# 01_Connector.net
KiCad netlist of a schematic drawn in Altium Designer
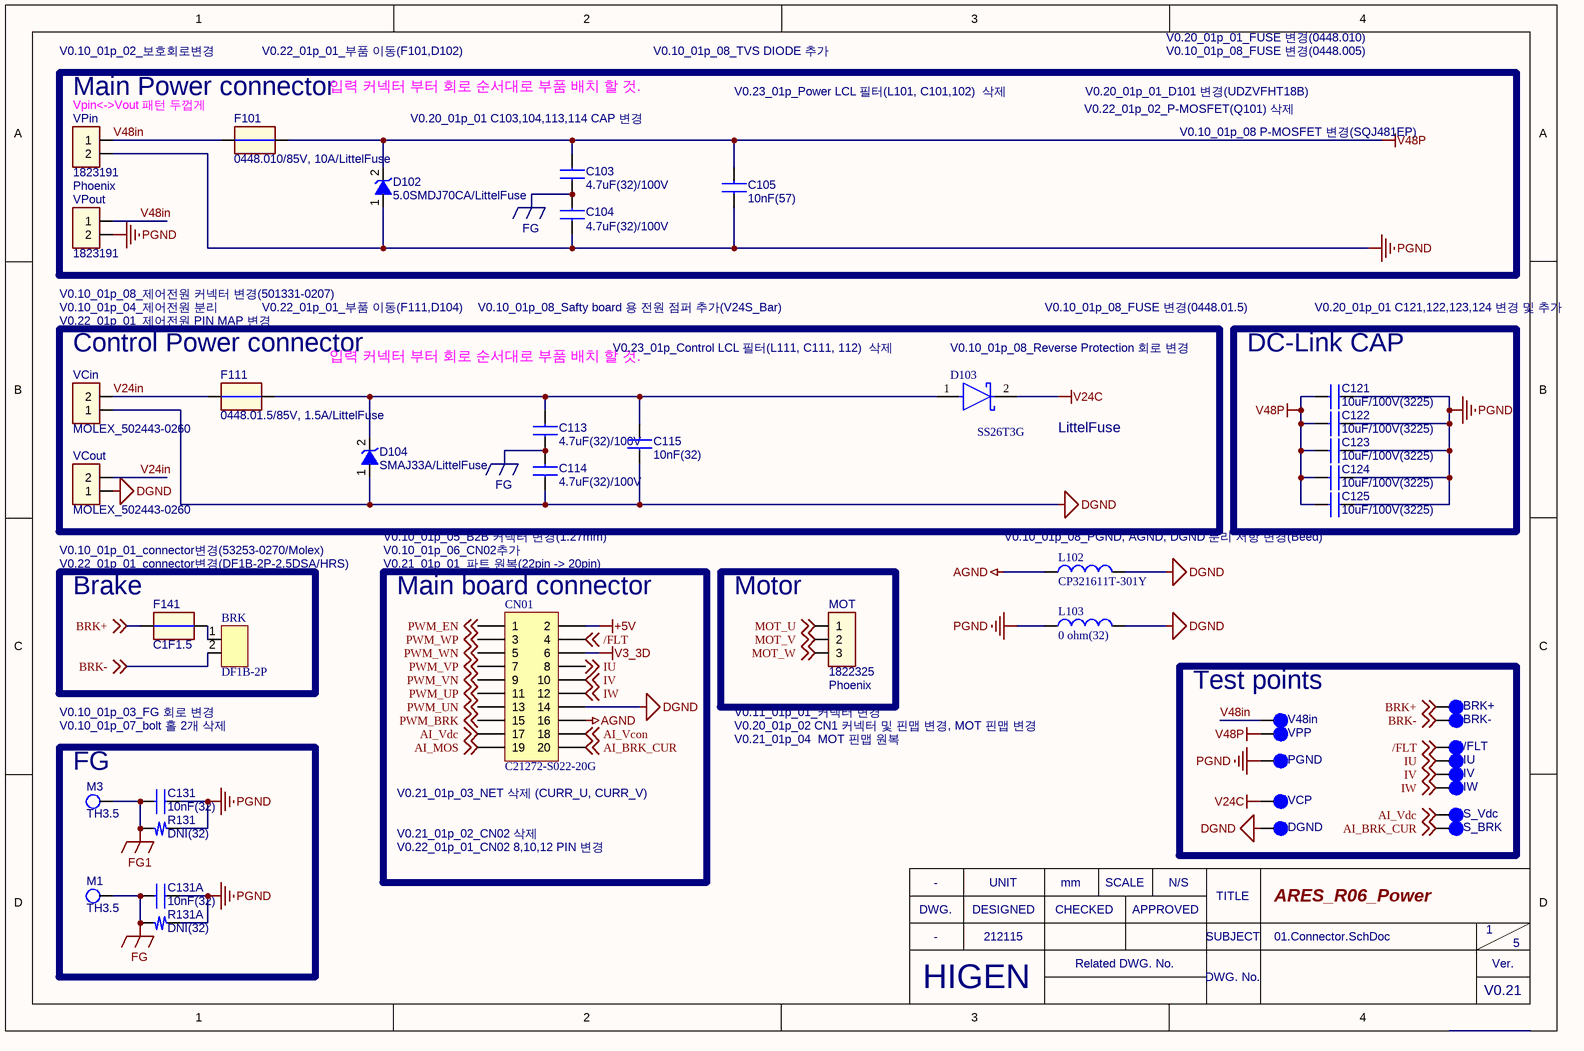
[diagram p0: 01.Connector.SchDoc]

(export (version "E")
  (design (tool "Eeschema 10.0.6"))
  (components
    (comp (ref "/FLT")
      (value "TP")
      (footprint "TP-SMD")
      (libsource (lib "*") (part "2H_TestPointThroughHole"))
    )
    (comp (ref "BRK")
      (value "DF1B-2P")
      (footprint "DF1B-2P-2.5DSA")
      (libsource (lib "DF1BB") (part "Component_1"))
    )
    (comp (ref "BRK+")
      (value "TP")
      (footprint "TP-SMD")
      (libsource (lib "*") (part "2H_TestPointThroughHole"))
    )
    (comp (ref "BRK-")
      (value "TP")
      (footprint "TP-SMD")
      (libsource (lib "*") (part "2H_TestPointThroughHole"))
    )
    (comp (ref "C103")
      (value "4.7uF(32)/100V")
      (footprint "C-3216S")
      (libsource (lib "HIGEN") (part "Cap_NP"))
    )
    (comp (ref "C104")
      (value "4.7uF(32)/100V")
      (footprint "C-3216S")
      (libsource (lib "HIGEN") (part "Cap_NP"))
    )
    (comp (ref "C105") (value "10nF(57)") (footprint "C-5750") (libsource (lib "HIGEN") (part "Cap_NP")))
    (comp (ref "C113")
      (value "4.7uF(32)/100V")
      (footprint "C-3216S")
      (libsource (lib "HIGEN") (part "Cap_NP"))
    )
    (comp (ref "C114")
      (value "4.7uF(32)/100V")
      (footprint "C-3216S")
      (libsource (lib "HIGEN") (part "Cap_NP"))
    )
    (comp (ref "C115") (value "10nF(32)") (footprint "C-3216S") (libsource (lib "HIGEN") (part "Cap_NP")))
    (comp (ref "C121")
      (value "10uF/100V(3225)")
      (footprint "C-3225")
      (libsource (lib "HIGEN") (part "Cap_NP"))
    )
    (comp (ref "C122")
      (value "10uF/100V(3225)")
      (footprint "C-3225")
      (libsource (lib "HIGEN") (part "Cap_NP"))
    )
    (comp (ref "C123")
      (value "10uF/100V(3225)")
      (footprint "C-3225")
      (libsource (lib "HIGEN") (part "Cap_NP"))
    )
    (comp (ref "C124")
      (value "10uF/100V(3225)")
      (footprint "C-3225")
      (libsource (lib "HIGEN") (part "Cap_NP"))
    )
    (comp (ref "C125")
      (value "10uF/100V(3225)")
      (footprint "C-3225")
      (libsource (lib "HIGEN") (part "Cap_NP"))
    )
    (comp (ref "C131") (value "10nF(32)") (footprint "C-3216S") (libsource (lib "HIGEN") (part "Cap_NP")))
    (comp (ref "C131A") (value "10nF(32)") (footprint "C-3216S") (libsource (lib "HIGEN") (part "Cap_NP")))
    (comp (ref "CN01")
      (value "C21272-S022-20G")
      (footprint "PH08SMD-D20P_PWR")
      (description "Header, 10-Pin, Dual row")
      (fields (field (name "PUBLISHER") "Altium Limited"))
      (libsource (lib "Miscellaneous Connectors") (part "Header 10X2"))
    )
    (comp (ref "D102")
      (value "5.0SMDJ70CA/LittelFuse")
      (footprint "DO-214AB")
      (libsource (lib "HIGEN") (part "Diode_TVS"))
    )
    (comp (ref "D103")
      (value "SS26T3G")
      (footprint "DO-214AA")
      (description "DIODE SCHOTTKY 60V 2A SMB")
      (fields
        (field (name "3DS PART NUMBER") "417-00001")
        (field (name "DIGIKEY PART NUMBER") "SS26T3GOSCT-ND")
      )
      (libsource (lib "EEConcierge") (part "SS26T3G"))
    )
    (comp (ref "D104")
      (value "SMAJ33A/LittelFuse")
      (footprint "SMA")
      (libsource (lib "HIGEN") (part "Diode_TVS"))
    )
    (comp (ref "DGND")
      (value "TP")
      (footprint "TP-SMD")
      (libsource (lib "*") (part "2H_TestPointThroughHole"))
    )
    (comp (ref "F101")
      (value "0448.010/85V, 10A/LittelFuse")
      (footprint "0448.005")
      (libsource (lib "") (part "Fuse_1"))
    )
    (comp (ref "F111")
      (value "0448.01.5/85V, 1.5A/LittelFuse")
      (footprint "0448.005")
      (libsource (lib "") (part "Fuse_1"))
    )
    (comp (ref "F141") (value "C1F1.5") (footprint "C-3216") (libsource (lib "HIGEN") (part "Fuse")))
    (comp (ref "IU") (value "TP") (footprint "TP-SMD") (libsource (lib "*") (part "2H_TestPointThroughHole")))
    (comp (ref "IV") (value "TP") (footprint "TP-SMD") (libsource (lib "*") (part "2H_TestPointThroughHole")))
    (comp (ref "IW") (value "TP") (footprint "TP-SMD") (libsource (lib "*") (part "2H_TestPointThroughHole")))
    (comp (ref "L102")
      (value "CP321611T-301Y")
      (footprint "L-3216")
      (description "Inductor")
      (fields (field (name "PUBLISHER") "Altium Limited"))
      (libsource (lib "Miscellaneous Devices") (part "Inductor"))
    )
    (comp (ref "L103")
      (value "0 ohm(32)")
      (footprint "L-3216")
      (description "Inductor")
      (fields (field (name "PUBLISHER") "Altium Limited"))
      (libsource (lib "Miscellaneous Devices") (part "Inductor"))
    )
    (comp (ref "M1") (value "TH3.5") (footprint "MH-3.5MM") (libsource (lib "HIGEN") (part "ThroughHole")))
    (comp (ref "M3") (value "TH3.5") (footprint "MH-3.5MM") (libsource (lib "HIGEN") (part "ThroughHole")))
    (comp (ref "MOT")
      (value "1822325")
      (footprint "1823191-3P")
      (libsource (lib "HIGEN") (part "Connector_1x3"))
    )
    (comp (ref "PGND")
      (value "TP")
      (footprint "TP-SMD")
      (libsource (lib "*") (part "2H_TestPointThroughHole"))
    )
    (comp (ref "R131")
      (value "DNI(32)")
      (footprint "R-3216S")
      (libsource (lib "AM437X_MAIN_LOW") (part "Res"))
    )
    (comp (ref "R131A")
      (value "DNI(32)")
      (footprint "R-3216S")
      (libsource (lib "AM437X_MAIN_LOW") (part "Res"))
    )
    (comp (ref "S_BRK")
      (value "TP")
      (footprint "TP-SMD")
      (libsource (lib "*") (part "2H_TestPointThroughHole"))
    )
    (comp (ref "S_Vdc")
      (value "TP")
      (footprint "TP-SMD")
      (libsource (lib "*") (part "2H_TestPointThroughHole"))
    )
    (comp (ref "V48in")
      (value "TP")
      (footprint "TP-SMD")
      (libsource (lib "*") (part "2H_TestPointThroughHole"))
    )
    (comp (ref "VCin")
      (value "MOLEX_502443-0260")
      (footprint "MOLEX_502443-0260")
      (libsource (lib "") (part "Connector_1x2_1"))
    )
    (comp (ref "VCout")
      (value "MOLEX_502443-0260")
      (footprint "MOLEX_502443-0260")
      (libsource (lib "") (part "Connector_1x2_1"))
    )
    (comp (ref "VCP")
      (value "TP")
      (footprint "TP-SMD")
      (libsource (lib "*") (part "2H_TestPointThroughHole"))
    )
    (comp (ref "VPin")
      (value "1823191")
      (footprint "1823191-2P")
      (libsource (lib "HIGEN") (part "Connector_1x2"))
    )
    (comp (ref "VPout")
      (value "1823191")
      (footprint "1823191-2P")
      (libsource (lib "HIGEN") (part "Connector_1x2"))
    )
    (comp (ref "VPP")
      (value "TP")
      (footprint "TP-SMD")
      (libsource (lib "*") (part "2H_TestPointThroughHole"))
    )
  )
  (nets
    (net (code "1") (name "+5V") (class "Default")
      (node (ref "CN01") (pin "2") (pinfunction "2_2") (pintype "passive"))
    )
    (net (code "2") (name "/V24in") (class "Default")
      (node (ref "F111") (pin "1") (pinfunction "1_1") (pintype "passive"))
      (node (ref "VCin") (pin "2") (pinfunction "2_2") (pintype "passive"))
      (node (ref "VCout") (pin "2") (pinfunction "2_2") (pintype "passive"))
    )
    (net (code "3") (name "/V48in") (class "Default")
      (node (ref "F101") (pin "1") (pinfunction "1_1") (pintype "passive"))
      (node (ref "V48in") (pin "1") (pinfunction "1_1") (pintype "passive"))
      (node (ref "VPin") (pin "1") (pinfunction "1_1") (pintype "passive"))
      (node (ref "VPout") (pin "1") (pinfunction "1_1") (pintype "passive"))
    )
    (net (code "4") (name "AGND") (class "Default")
      (node (ref "CN01") (pin "16") (pinfunction "16_16") (pintype "passive"))
      (node (ref "L102") (pin "1") (pinfunction "1_1") (pintype "passive"))
    )
    (net (code "5") (name "AI_BRK_CUR") (class "Default")
      (node (ref "CN01") (pin "20") (pinfunction "20_20") (pintype "passive"))
      (node (ref "S_BRK") (pin "1") (pinfunction "1_1") (pintype "passive"))
    )
    (net (code "6") (name "AI_MOS") (class "Default")
      (node (ref "CN01") (pin "19") (pinfunction "19_19") (pintype "passive"))
    )
    (net (code "7") (name "AI_Vcon") (class "Default")
      (node (ref "CN01") (pin "18") (pinfunction "18_18") (pintype "passive"))
    )
    (net (code "8") (name "AI_Vdc") (class "Default")
      (node (ref "CN01") (pin "17") (pinfunction "17_17") (pintype "passive"))
      (node (ref "S_Vdc") (pin "1") (pinfunction "1_1") (pintype "passive"))
    )
    (net (code "9") (name "BRK+") (class "Default")
      (node (ref "BRK+") (pin "1") (pinfunction "1_1") (pintype "passive"))
      (node (ref "F141") (pin "2") (pinfunction "2_2") (pintype "passive"))
    )
    (net (code "10") (name "BRK-") (class "Default")
      (node (ref "BRK") (pin "2") (pinfunction "2_2") (pintype "passive"))
      (node (ref "BRK-") (pin "1") (pinfunction "1_1") (pintype "passive"))
    )
    (net (code "11") (name "DGND") (class "Default")
      (node (ref "C114") (pin "1") (pinfunction "1_1") (pintype "passive"))
      (node (ref "C115") (pin "1") (pinfunction "1_1") (pintype "passive"))
      (node (ref "CN01") (pin "14") (pinfunction "14_14") (pintype "passive"))
      (node (ref "D104") (pin "1") (pinfunction "A_1") (pintype "passive"))
      (node (ref "DGND") (pin "1") (pinfunction "1_1") (pintype "passive"))
      (node (ref "L102") (pin "2") (pinfunction "2_2") (pintype "passive"))
      (node (ref "L103") (pin "2") (pinfunction "2_2") (pintype "passive"))
      (node (ref "VCin") (pin "1") (pinfunction "1_1") (pintype "passive"))
      (node (ref "VCout") (pin "1") (pinfunction "1_1") (pintype "passive"))
    )
    (net (code "12") (name "FG") (class "Default")
      (node (ref "C103") (pin "1") (pinfunction "1_1") (pintype "passive"))
      (node (ref "C104") (pin "2") (pinfunction "2_2") (pintype "passive"))
      (node (ref "C113") (pin "1") (pinfunction "1_1") (pintype "passive"))
      (node (ref "C114") (pin "2") (pinfunction "2_2") (pintype "passive"))
      (node (ref "C131A") (pin "1") (pinfunction "1_1") (pintype "passive"))
      (node (ref "M1") (pin "1") (pinfunction "TP_1") (pintype "passive"))
      (node (ref "R131A") (pin "1") (pinfunction "P1_1") (pintype "passive"))
    )
    (net (code "13") (name "FG1") (class "Default")
      (node (ref "C131") (pin "1") (pinfunction "1_1") (pintype "passive"))
      (node (ref "M3") (pin "1") (pinfunction "TP_1") (pintype "passive"))
      (node (ref "R131") (pin "1") (pinfunction "P1_1") (pintype "passive"))
    )
    (net (code "14") (name "IU") (class "Default")
      (node (ref "CN01") (pin "8") (pinfunction "8_8") (pintype "passive"))
      (node (ref "IU") (pin "1") (pinfunction "1_1") (pintype "passive"))
    )
    (net (code "15") (name "IV") (class "Default")
      (node (ref "CN01") (pin "10") (pinfunction "10_10") (pintype "passive"))
      (node (ref "IV") (pin "1") (pinfunction "1_1") (pintype "passive"))
    )
    (net (code "16") (name "IW") (class "Default")
      (node (ref "CN01") (pin "12") (pinfunction "12_12") (pintype "passive"))
      (node (ref "IW") (pin "1") (pinfunction "1_1") (pintype "passive"))
    )
    (net (code "17") (name "MOT_U") (class "Default")
      (node (ref "MOT") (pin "1") (pinfunction "1_1") (pintype "passive"))
    )
    (net (code "18") (name "MOT_V") (class "Default")
      (node (ref "MOT") (pin "2") (pinfunction "2_2") (pintype "passive"))
    )
    (net (code "19") (name "MOT_W") (class "Default")
      (node (ref "MOT") (pin "3") (pinfunction "3_3") (pintype "passive"))
    )
    (net (code "20") (name "Net-(BRK-2-Pad1)") (class "Default")
      (node (ref "BRK") (pin "1") (pinfunction "2_1") (pintype "passive"))
      (node (ref "F141") (pin "1") (pinfunction "1_1") (pintype "passive"))
    )
    (net (code "21") (name "Net-(D103-A)") (class "Default")
      (node (ref "C113") (pin "2") (pinfunction "2_2") (pintype "passive"))
      (node (ref "C115") (pin "2") (pinfunction "2_2") (pintype "passive"))
      (node (ref "D103") (pin "1") (pinfunction "A_1") (pintype "passive"))
      (node (ref "D104") (pin "2") (pinfunction "K_2") (pintype "passive"))
      (node (ref "F111") (pin "2") (pinfunction "2_2") (pintype "passive"))
    )
    (net (code "22") (name "PGND") (class "Default")
      (node (ref "C104") (pin "1") (pinfunction "1_1") (pintype "passive"))
      (node (ref "C105") (pin "1") (pinfunction "1_1") (pintype "passive"))
      (node (ref "C121") (pin "2") (pinfunction "2_2") (pintype "passive"))
      (node (ref "C122") (pin "2") (pinfunction "2_2") (pintype "passive"))
      (node (ref "C123") (pin "2") (pinfunction "2_2") (pintype "passive"))
      (node (ref "C124") (pin "2") (pinfunction "2_2") (pintype "passive"))
      (node (ref "C125") (pin "2") (pinfunction "2_2") (pintype "passive"))
      (node (ref "C131") (pin "2") (pinfunction "2_2") (pintype "passive"))
      (node (ref "C131A") (pin "2") (pinfunction "2_2") (pintype "passive"))
      (node (ref "D102") (pin "1") (pinfunction "A_1") (pintype "passive"))
      (node (ref "L103") (pin "1") (pinfunction "1_1") (pintype "passive"))
      (node (ref "PGND") (pin "1") (pinfunction "1_1") (pintype "passive"))
      (node (ref "R131") (pin "2") (pinfunction "P2_2") (pintype "passive"))
      (node (ref "R131A") (pin "2") (pinfunction "P2_2") (pintype "passive"))
      (node (ref "VPin") (pin "2") (pinfunction "2_2") (pintype "passive"))
      (node (ref "VPout") (pin "2") (pinfunction "2_2") (pintype "passive"))
    )
    (net (code "23") (name "PWM_BRK") (class "Default")
      (node (ref "CN01") (pin "15") (pinfunction "15_15") (pintype "passive"))
    )
    (net (code "24") (name "PWM_EN") (class "Default")
      (node (ref "CN01") (pin "1") (pinfunction "1_1") (pintype "passive"))
    )
    (net (code "25") (name "PWM_UN") (class "Default")
      (node (ref "CN01") (pin "13") (pinfunction "13_13") (pintype "passive"))
    )
    (net (code "26") (name "PWM_UP") (class "Default")
      (node (ref "CN01") (pin "11") (pinfunction "11_11") (pintype "passive"))
    )
    (net (code "27") (name "PWM_VN") (class "Default")
      (node (ref "CN01") (pin "9") (pinfunction "9_9") (pintype "passive"))
    )
    (net (code "28") (name "PWM_VP") (class "Default")
      (node (ref "CN01") (pin "7") (pinfunction "7_7") (pintype "passive"))
    )
    (net (code "29") (name "PWM_WN") (class "Default")
      (node (ref "CN01") (pin "5") (pinfunction "5_5") (pintype "passive"))
    )
    (net (code "30") (name "PWM_WP") (class "Default")
      (node (ref "CN01") (pin "3") (pinfunction "3_3") (pintype "passive"))
    )
    (net (code "31") (name "V3_3D") (class "Default")
      (node (ref "CN01") (pin "6") (pinfunction "6_6") (pintype "passive"))
    )
    (net (code "32") (name "V24C") (class "Default")
      (node (ref "D103") (pin "2") (pinfunction "C_2") (pintype "passive"))
      (node (ref "VCP") (pin "1") (pinfunction "1_1") (pintype "passive"))
    )
    (net (code "33") (name "V48P") (class "Default")
      (node (ref "C103") (pin "2") (pinfunction "2_2") (pintype "passive"))
      (node (ref "C105") (pin "2") (pinfunction "2_2") (pintype "passive"))
      (node (ref "C121") (pin "1") (pinfunction "1_1") (pintype "passive"))
      (node (ref "C122") (pin "1") (pinfunction "1_1") (pintype "passive"))
      (node (ref "C123") (pin "1") (pinfunction "1_1") (pintype "passive"))
      (node (ref "C124") (pin "1") (pinfunction "1_1") (pintype "passive"))
      (node (ref "C125") (pin "1") (pinfunction "1_1") (pintype "passive"))
      (node (ref "D102") (pin "2") (pinfunction "K_2") (pintype "passive"))
      (node (ref "F101") (pin "2") (pinfunction "2_2") (pintype "passive"))
      (node (ref "VPP") (pin "1") (pinfunction "1_1") (pintype "passive"))
    )
    (net (code "34") (name "{slash}FLT") (class "Default")
      (node (ref "/FLT") (pin "1") (pinfunction "1_1") (pintype "passive"))
      (node (ref "CN01") (pin "4") (pinfunction "4_4") (pintype "passive"))
    )
  )
)
